# PowerSupply.net
KiCad netlist of a schematic drawn in EAGLE
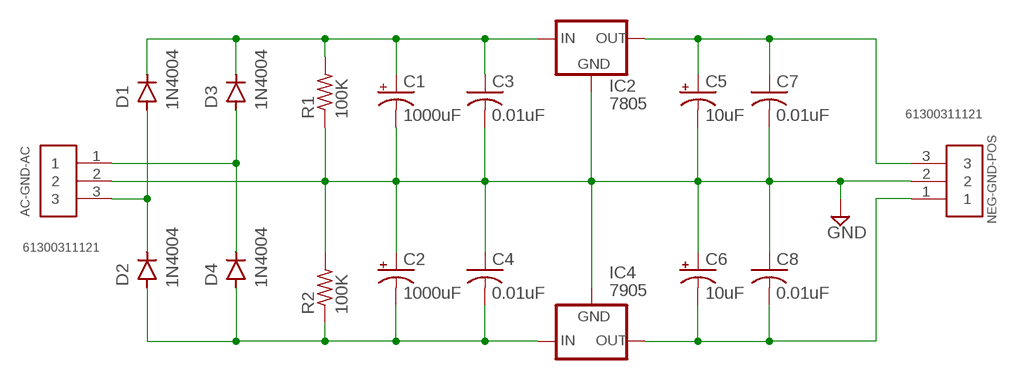
[diagram p0: schematic, sheet 1]

(export (version "E")
  (design (tool "Eeschema 10.0.6"))
  (components
    (comp (ref "AC-GND-AC")
      (value "61300311121")
      (footprint "eagle-import:61300311121")
      (fields
        (field (name "DIGI_KEY_PART_NUMBER") "732-5316-ND")
        (field (name "MANUFACTURER") "Wurth Electronics Inc.")
        (field (name "CREATED_BY") "PCBLayout.com")
      )
      (libsource (lib "eagle-import") (part "61300311121"))
    )
    (comp (ref "C1")
      (value "1000uF")
      (footprint "eagle-import:E3,5-8")
      (libsource (lib "eagle-import") (part "CPOL-USE3.5-8"))
    )
    (comp (ref "C2")
      (value "1000uF")
      (footprint "eagle-import:E3,5-8")
      (libsource (lib "eagle-import") (part "CPOL-USE3.5-8"))
    )
    (comp (ref "C3")
      (value "0.01uF")
      (footprint "eagle-import:C050-025X075")
      (libsource (lib "eagle-import") (part "C-US050-025X075"))
    )
    (comp (ref "C4")
      (value "0.01uF")
      (footprint "eagle-import:C050-025X075")
      (libsource (lib "eagle-import") (part "C-US050-025X075"))
    )
    (comp (ref "C5")
      (value "10uF")
      (footprint "eagle-import:E2,5-6")
      (libsource (lib "eagle-import") (part "CPOL-USE2.5-6"))
    )
    (comp (ref "C6")
      (value "10uF")
      (footprint "eagle-import:E2,5-6")
      (libsource (lib "eagle-import") (part "CPOL-USE2.5-6"))
    )
    (comp (ref "C7")
      (value "0.01uF")
      (footprint "eagle-import:C050-025X075")
      (libsource (lib "eagle-import") (part "C-US050-025X075"))
    )
    (comp (ref "C8")
      (value "0.01uF")
      (footprint "eagle-import:C050-025X075")
      (libsource (lib "eagle-import") (part "C-US050-025X075"))
    )
    (comp (ref "D1")
      (value "1N4004")
      (footprint "eagle-import:DO-41")
      (fields
        (field (name "DIGIKEY_PART_NUMBER") "1N4004MSCT-ND")
        (field (name "MANUFACTURER") "Micro Commercial Co")
        (field (name "CREATED_BY") "PCBLayout.com")
      )
      (libsource (lib "eagle-import") (part "1N4004"))
    )
    (comp (ref "D2")
      (value "1N4004")
      (footprint "eagle-import:DO-41")
      (fields
        (field (name "DIGIKEY_PART_NUMBER") "1N4004MSCT-ND")
        (field (name "MANUFACTURER") "Micro Commercial Co")
        (field (name "CREATED_BY") "PCBLayout.com")
      )
      (libsource (lib "eagle-import") (part "1N4004"))
    )
    (comp (ref "D3")
      (value "1N4004")
      (footprint "eagle-import:DO-41")
      (fields
        (field (name "DIGIKEY_PART_NUMBER") "1N4004MSCT-ND")
        (field (name "MANUFACTURER") "Micro Commercial Co")
        (field (name "CREATED_BY") "PCBLayout.com")
      )
      (libsource (lib "eagle-import") (part "1N4004"))
    )
    (comp (ref "D4")
      (value "1N4004")
      (footprint "eagle-import:DO-41")
      (fields
        (field (name "DIGIKEY_PART_NUMBER") "1N4004MSCT-ND")
        (field (name "MANUFACTURER") "Micro Commercial Co")
        (field (name "CREATED_BY") "PCBLayout.com")
      )
      (libsource (lib "eagle-import") (part "1N4004"))
    )
    (comp (ref "IC2")
      (value "7805")
      (footprint "eagle-import:78XXS")
      (libsource (lib "eagle-import") (part "78XXS"))
    )
    (comp (ref "IC4")
      (value "7905")
      (footprint "eagle-import:79XXS")
      (libsource (lib "eagle-import") (part "79XXS"))
    )
    (comp (ref "NEG-GND-POS")
      (value "61300311121")
      (footprint "eagle-import:61300311121")
      (fields
        (field (name "DIGI_KEY_PART_NUMBER") "732-5316-ND")
        (field (name "MANUFACTURER") "Wurth Electronics Inc.")
        (field (name "CREATED_BY") "PCBLayout.com")
      )
      (libsource (lib "eagle-import") (part "61300311121"))
    )
    (comp (ref "R1")
      (value "100K")
      (footprint "eagle-import:0411_12")
      (libsource (lib "eagle-import") (part "R-US_0411/12"))
    )
    (comp (ref "R2")
      (value "100K")
      (footprint "eagle-import:0411_12")
      (libsource (lib "eagle-import") (part "R-US_0411/12"))
    )
  )
  (nets
    (net (code "1") (name "GND") (class "Default")
      (node (ref "AC-GND-AC") (pin "2") (pinfunction "2_2") (pintype "passive"))
      (node (ref "C1") (pin "-") (pinfunction "-_-") (pintype "passive"))
      (node (ref "C2") (pin "+") (pinfunction "+_+") (pintype "passive"))
      (node (ref "C3") (pin "2") (pinfunction "2_2") (pintype "passive"))
      (node (ref "C4") (pin "1") (pinfunction "1_1") (pintype "passive"))
      (node (ref "C5") (pin "-") (pinfunction "-_-") (pintype "passive"))
      (node (ref "C6") (pin "+") (pinfunction "+_+") (pintype "passive"))
      (node (ref "C7") (pin "2") (pinfunction "2_2") (pintype "passive"))
      (node (ref "C8") (pin "1") (pinfunction "1_1") (pintype "passive"))
      (node (ref "IC2") (pin "GND") (pinfunction "GND_GND") (pintype "input"))
      (node (ref "IC4") (pin "GND") (pinfunction "GND_GND") (pintype "input"))
      (node (ref "NEG-GND-POS") (pin "2") (pinfunction "2_2") (pintype "passive"))
      (node (ref "R1") (pin "1") (pinfunction "1_1") (pintype "passive"))
      (node (ref "R2") (pin "2") (pinfunction "2_2") (pintype "passive"))
    )
    (net (code "2") (name "Net-(AC-GND-AC-Pad1)") (class "Default")
      (node (ref "AC-GND-AC") (pin "1") (pinfunction "1_1") (pintype "passive"))
      (node (ref "D3") (pin "A") (pinfunction "A_A") (pintype "passive"))
      (node (ref "D4") (pin "C") (pinfunction "C_C") (pintype "passive"))
    )
    (net (code "3") (name "Net-(AC-GND-AC-Pad3)") (class "Default")
      (node (ref "AC-GND-AC") (pin "3") (pinfunction "3_3") (pintype "passive"))
      (node (ref "D1") (pin "A") (pinfunction "A_A") (pintype "passive"))
      (node (ref "D2") (pin "C") (pinfunction "C_C") (pintype "passive"))
    )
    (net (code "4") (name "Net-(C1-Pad+)") (class "Default")
      (node (ref "C1") (pin "+") (pinfunction "+_+") (pintype "passive"))
      (node (ref "C3") (pin "1") (pinfunction "1_1") (pintype "passive"))
      (node (ref "D1") (pin "C") (pinfunction "C_C") (pintype "passive"))
      (node (ref "D3") (pin "C") (pinfunction "C_C") (pintype "passive"))
      (node (ref "IC2") (pin "IN") (pinfunction "IN_IN") (pintype "input"))
      (node (ref "R1") (pin "2") (pinfunction "2_2") (pintype "passive"))
    )
    (net (code "5") (name "Net-(C2-Pad-)") (class "Default")
      (node (ref "C2") (pin "-") (pinfunction "-_-") (pintype "passive"))
      (node (ref "C4") (pin "2") (pinfunction "2_2") (pintype "passive"))
      (node (ref "D2") (pin "A") (pinfunction "A_A") (pintype "passive"))
      (node (ref "D4") (pin "A") (pinfunction "A_A") (pintype "passive"))
      (node (ref "IC4") (pin "IN") (pinfunction "IN_IN") (pintype "input"))
      (node (ref "R2") (pin "1") (pinfunction "1_1") (pintype "passive"))
    )
    (net (code "6") (name "Net-(C5-Pad+)") (class "Default")
      (node (ref "C5") (pin "+") (pinfunction "+_+") (pintype "passive"))
      (node (ref "C7") (pin "1") (pinfunction "1_1") (pintype "passive"))
      (node (ref "IC2") (pin "OUT") (pinfunction "OUT_OUT") (pintype "passive"))
      (node (ref "NEG-GND-POS") (pin "3") (pinfunction "3_3") (pintype "passive"))
    )
    (net (code "7") (name "Net-(C6-Pad-)") (class "Default")
      (node (ref "C6") (pin "-") (pinfunction "-_-") (pintype "passive"))
      (node (ref "C8") (pin "2") (pinfunction "2_2") (pintype "passive"))
      (node (ref "IC4") (pin "OUT") (pinfunction "OUT_OUT") (pintype "passive"))
      (node (ref "NEG-GND-POS") (pin "1") (pinfunction "1_1") (pintype "passive"))
    )
  )
)
